# spsu.net
KiCad netlist of a schematic drawn in EAGLE
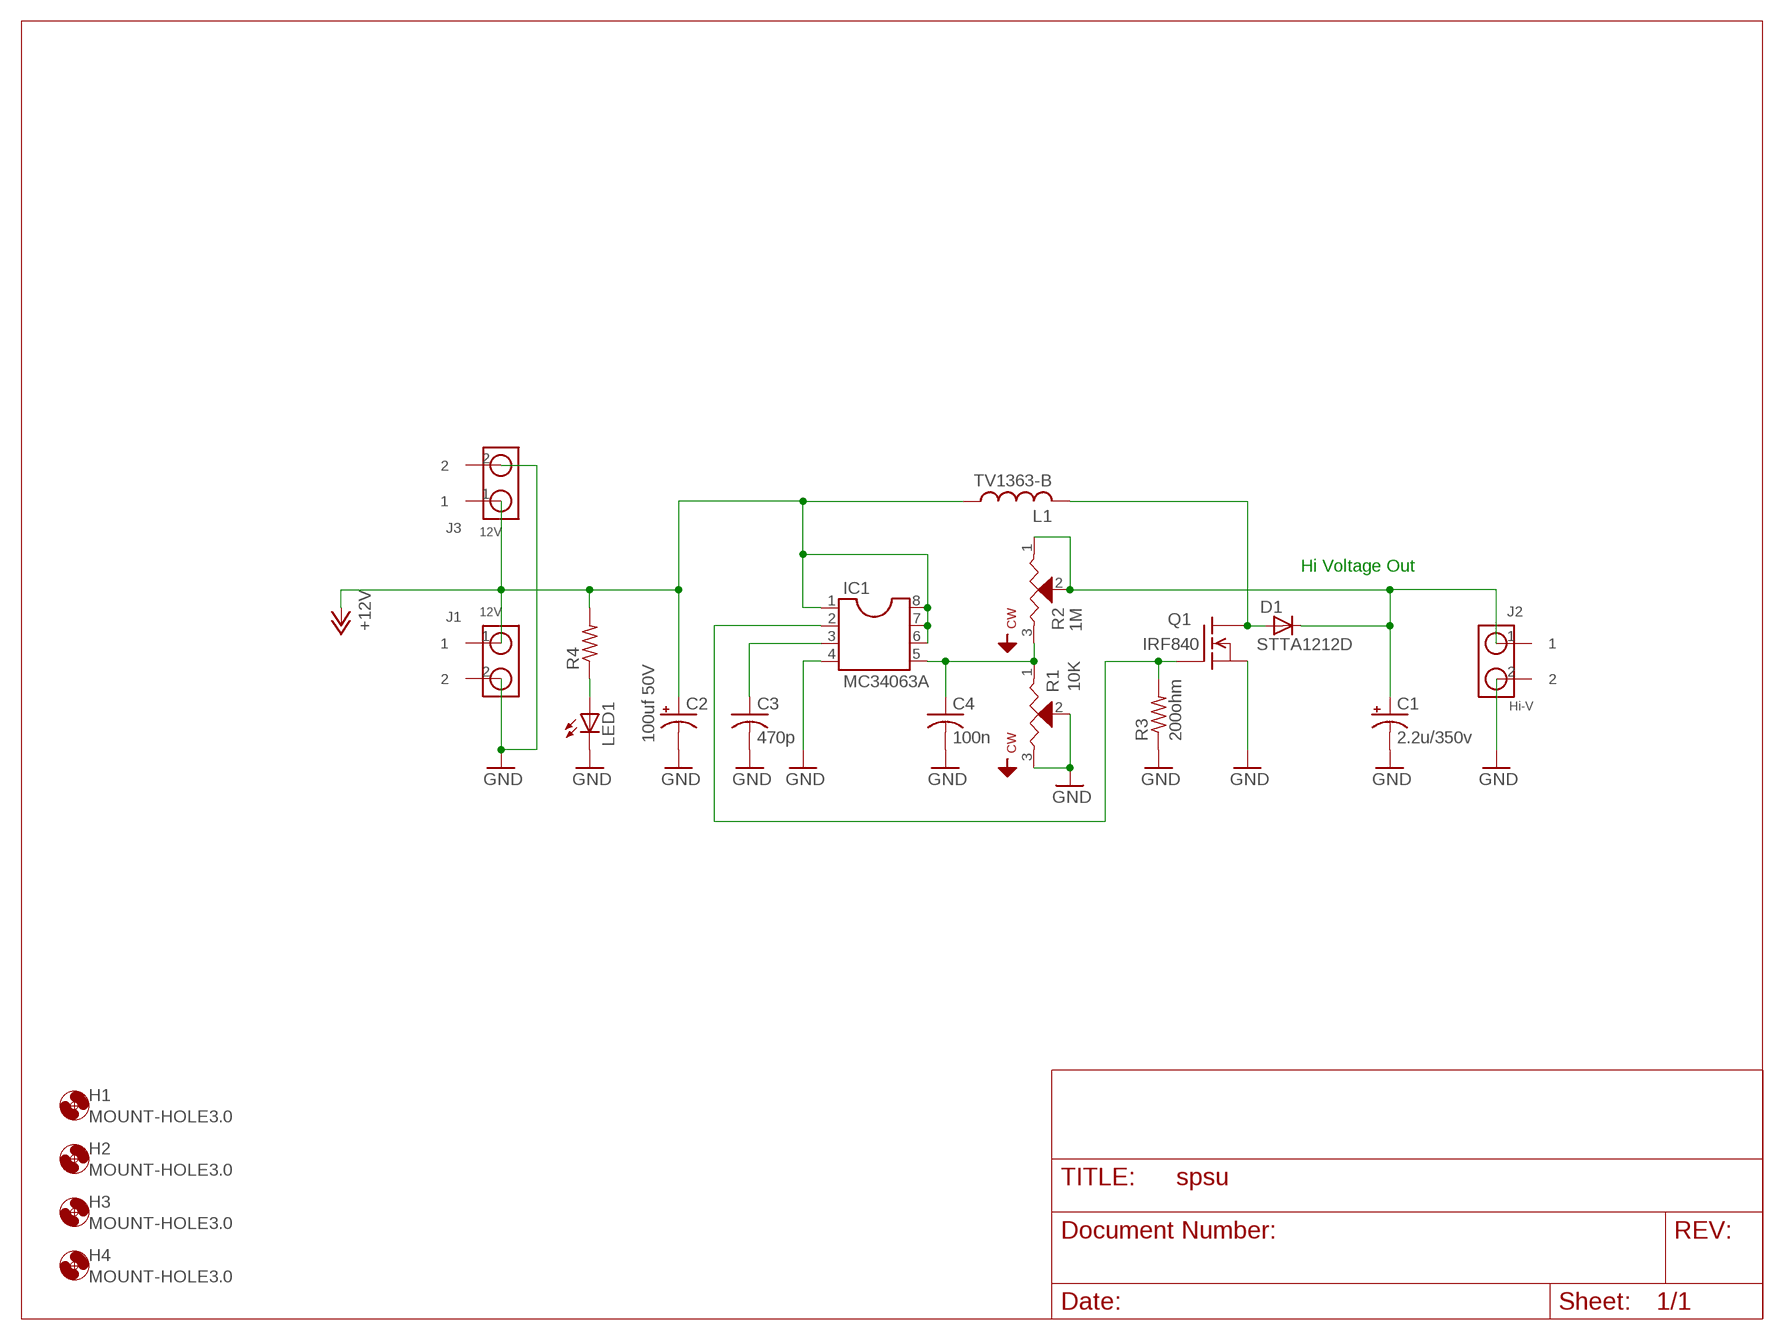
[diagram p0: schematic, sheet 1]

(export (version "E")
  (design (tool "Eeschema 10.0.6"))
  (components
    (comp (ref "C1")
      (value "2.2u/350v")
      (footprint "eagle-import:E5-8,5")
      (libsource (lib "eagle-import") (part "CPOL-USE5-8.5"))
    )
    (comp (ref "C2")
      (value "100uf 50V")
      (footprint "eagle-import:E5-8,5")
      (libsource (lib "eagle-import") (part "CPOL-USE5-8.5"))
    )
    (comp (ref "C3")
      (value "470p")
      (footprint "eagle-import:C025-040X050")
      (libsource (lib "eagle-import") (part "C-US025-040X050"))
    )
    (comp (ref "C4")
      (value "100n")
      (footprint "eagle-import:C025-040X050")
      (libsource (lib "eagle-import") (part "C-US025-040X050"))
    )
    (comp (ref "D1")
      (value "STTA1212D")
      (footprint "eagle-import:TO220ACS")
      (libsource (lib "eagle-import") (part "STTA1212D"))
    )
    (comp (ref "H1")
      (value "MOUNT-HOLE3.0")
      (footprint "eagle-import:3,0")
      (libsource (lib "eagle-import") (part "MOUNT-HOLE3.0"))
    )
    (comp (ref "H2")
      (value "MOUNT-HOLE3.0")
      (footprint "eagle-import:3,0")
      (libsource (lib "eagle-import") (part "MOUNT-HOLE3.0"))
    )
    (comp (ref "H3")
      (value "MOUNT-HOLE3.0")
      (footprint "eagle-import:3,0")
      (libsource (lib "eagle-import") (part "MOUNT-HOLE3.0"))
    )
    (comp (ref "H4")
      (value "MOUNT-HOLE3.0")
      (footprint "eagle-import:3,0")
      (libsource (lib "eagle-import") (part "MOUNT-HOLE3.0"))
    )
    (comp (ref "IC1")
      (value "MC34063A")
      (footprint "eagle-import:DIL08")
      (libsource (lib "eagle-import") (part "MC34063A"))
    )
    (comp (ref "J1")
      (value "12V")
      (footprint "eagle-import:MOLEX-001-2PIN")
      (libsource (lib "eagle-import") (part "MOLEX-2PIN-BASE"))
    )
    (comp (ref "J2")
      (value "Hi-V")
      (footprint "eagle-import:MOLEX-001-2PIN")
      (libsource (lib "eagle-import") (part "MOLEX-2PIN-BASE"))
    )
    (comp (ref "J3")
      (value "12V")
      (footprint "eagle-import:MOLEX-001-2PIN")
      (libsource (lib "eagle-import") (part "MOLEX-2PIN-BASE"))
    )
    (comp (ref "L1")
      (value "TV1363-B")
      (footprint "eagle-import:RADIAL-VMOUNT-8-5MM")
      (libsource (lib "eagle-import") (part "TV1363-B-COIL"))
    )
    (comp (ref "LED1")
      (value "LED3MM")
      (footprint "eagle-import:LED3MM")
      (libsource (lib "eagle-import") (part "LED3MM"))
    )
    (comp (ref "Q1")
      (value "IRF840")
      (footprint "eagle-import:TO220V")
      (libsource (lib "eagle-import") (part "IRF840-FET"))
    )
    (comp (ref "R1")
      (value "10K")
      (footprint "eagle-import:.25IN-TOP-TRIMPOT")
      (libsource (lib "eagle-import") (part ".25SQ-TOPADJ-TRIMPOT"))
    )
    (comp (ref "R2")
      (value "1M")
      (footprint "eagle-import:.25IN-TOP-TRIMPOT")
      (libsource (lib "eagle-import") (part ".25SQ-TOPADJ-TRIMPOT"))
    )
    (comp (ref "R3")
      (value "200ohm")
      (footprint "eagle-import:0204_5")
      (libsource (lib "eagle-import") (part "R-US_0204/5"))
    )
    (comp (ref "R4")
      (value "R-US_0204/5")
      (footprint "eagle-import:0204_5")
      (libsource (lib "eagle-import") (part "R-US_0204/5"))
    )
  )
  (nets
    (net (code "1") (name "+12V") (class "Default")
      (node (ref "C2") (pin "+") (pinfunction "+_+") (pintype "passive"))
      (node (ref "IC1") (pin "1") (pinfunction "1_1") (pintype "passive"))
      (node (ref "IC1") (pin "6") (pinfunction "6_6") (pintype "passive"))
      (node (ref "IC1") (pin "7") (pinfunction "7_7") (pintype "passive"))
      (node (ref "IC1") (pin "8") (pinfunction "8_8") (pintype "passive"))
      (node (ref "J1") (pin "1") (pinfunction "1_1") (pintype "passive"))
      (node (ref "J3") (pin "1") (pinfunction "1_1") (pintype "passive"))
      (node (ref "L1") (pin "1") (pinfunction "1_1") (pintype "passive"))
      (node (ref "R4") (pin "2") (pinfunction "2_2") (pintype "passive"))
    )
    (net (code "2") (name "GND") (class "Default")
      (node (ref "C1") (pin "-") (pinfunction "-_-") (pintype "passive"))
      (node (ref "C2") (pin "-") (pinfunction "-_-") (pintype "passive"))
      (node (ref "C3") (pin "2") (pinfunction "2_2") (pintype "passive"))
      (node (ref "C4") (pin "2") (pinfunction "2_2") (pintype "passive"))
      (node (ref "IC1") (pin "4") (pinfunction "4_4") (pintype "passive"))
      (node (ref "J1") (pin "2") (pinfunction "2_2") (pintype "passive"))
      (node (ref "J2") (pin "2") (pinfunction "2_2") (pintype "passive"))
      (node (ref "J3") (pin "2") (pinfunction "2_2") (pintype "passive"))
      (node (ref "LED1") (pin "K") (pinfunction "C_K") (pintype "passive"))
      (node (ref "Q1") (pin "3") (pinfunction "S_3") (pintype "passive"))
      (node (ref "R1") (pin "2") (pinfunction "2_2") (pintype "passive"))
      (node (ref "R1") (pin "3") (pinfunction "3_3") (pintype "passive"))
      (node (ref "R3") (pin "1") (pinfunction "1_1") (pintype "passive"))
    )
    (net (code "3") (name "Net-(C1-Pad+)") (class "Default")
      (node (ref "C1") (pin "+") (pinfunction "+_+") (pintype "passive"))
      (node (ref "D1") (pin "C") (pinfunction "C_C") (pintype "passive"))
      (node (ref "J2") (pin "1") (pinfunction "1_1") (pintype "passive"))
      (node (ref "R2") (pin "1") (pinfunction "1_1") (pintype "passive"))
      (node (ref "R2") (pin "2") (pinfunction "2_2") (pintype "passive"))
    )
    (net (code "4") (name "Net-(C3-Pad1)") (class "Default")
      (node (ref "C3") (pin "1") (pinfunction "1_1") (pintype "passive"))
      (node (ref "IC1") (pin "3") (pinfunction "3_3") (pintype "passive"))
    )
    (net (code "5") (name "Net-(C4-Pad1)") (class "Default")
      (node (ref "C4") (pin "1") (pinfunction "1_1") (pintype "passive"))
      (node (ref "IC1") (pin "5") (pinfunction "5_5") (pintype "passive"))
      (node (ref "R1") (pin "1") (pinfunction "1_1") (pintype "passive"))
      (node (ref "R2") (pin "3") (pinfunction "3_3") (pintype "passive"))
    )
    (net (code "6") (name "Net-(LED1-PadA)") (class "Default")
      (node (ref "LED1") (pin "A") (pinfunction "A_A") (pintype "passive"))
      (node (ref "R4") (pin "1") (pinfunction "1_1") (pintype "passive"))
    )
    (net (code "7") (name "Net-(Q1-D)") (class "Default")
      (node (ref "D1") (pin "A") (pinfunction "A_A") (pintype "passive"))
      (node (ref "L1") (pin "2") (pinfunction "2_2") (pintype "passive"))
      (node (ref "Q1") (pin "2") (pinfunction "D_2") (pintype "passive"))
    )
    (net (code "8") (name "Net-(Q1-G)") (class "Default")
      (node (ref "IC1") (pin "2") (pinfunction "2_2") (pintype "passive"))
      (node (ref "Q1") (pin "1") (pinfunction "G_1") (pintype "passive"))
      (node (ref "R3") (pin "2") (pinfunction "2_2") (pintype "passive"))
    )
  )
)
